# Copy_of_electretMicPreamp_-_THT.net
KiCad netlist of a schematic drawn in EAGLE
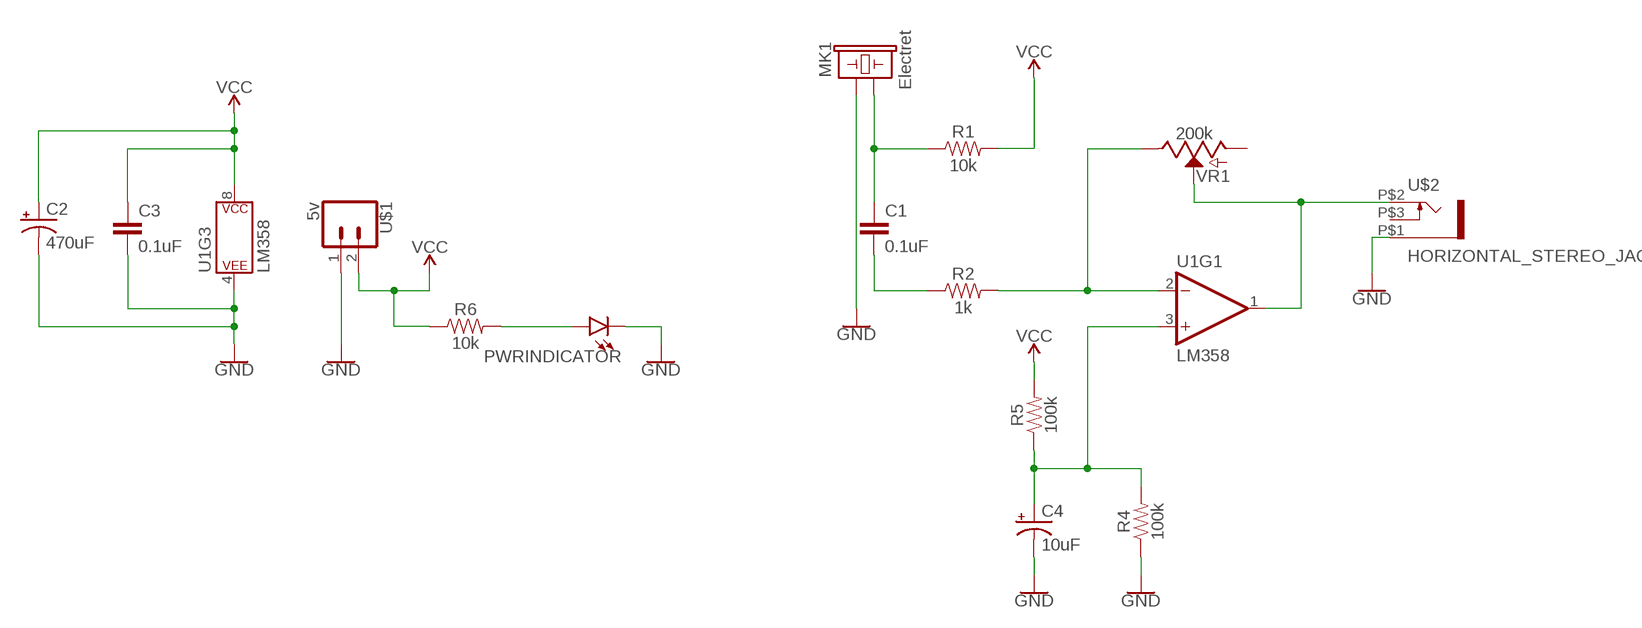
[diagram p0: schematic, sheet 1]

(export (version "E")
  (design (tool "Eeschema 10.0.6"))
  (components
    (comp (ref "C1")
      (value "0.1uF")
      (footprint "eagle-import:CAP-PTH-SMALL-KIT")
      (libsource (lib "eagle-import") (part "0.1UF-KIT-EZ-50V-20%"))
    )
    (comp (ref "C2")
      (value "470uF")
      (footprint "eagle-import:CPOL-RADIAL-2.5MM-5MM")
      (libsource (lib "eagle-import") (part "10UF-POLAR-RADIAL-2.5MM-25V-20%"))
    )
    (comp (ref "C3")
      (value "0.1uF")
      (footprint "eagle-import:CAP-PTH-SMALL-KIT")
      (libsource (lib "eagle-import") (part "0.1UF-KIT-EZ-50V-20%"))
    )
    (comp (ref "C4")
      (value "10uF")
      (footprint "eagle-import:CPOL-RADIAL-2.5MM-5MM")
      (libsource (lib "eagle-import") (part "10UF-POLAR-RADIAL-2.5MM-25V-20%"))
    )
    (comp (ref "MK1")
      (value "Electret")
      (footprint "eagle-import:MICROPHONE-PTH-9.7MM")
      (libsource (lib "eagle-import") (part "MIC-PTH"))
    )
    (comp (ref "PWRINDICATOR")
      (value "LED-3MM-NO_SILK")
      (footprint "eagle-import:LED_3MM-NS")
      (libsource (lib "eagle-import") (part "LED-3MM-NO_SILK"))
    )
    (comp (ref "R1")
      (value "10k")
      (footprint "eagle-import:AXIAL-0.3")
      (libsource (lib "eagle-import") (part "1KOHM-HORIZ-1/4W-5%"))
    )
    (comp (ref "R2")
      (value "1k")
      (footprint "eagle-import:AXIAL-0.3")
      (libsource (lib "eagle-import") (part "1KOHM-HORIZ-1/4W-5%"))
    )
    (comp (ref "R4")
      (value "100k")
      (footprint "eagle-import:AXIAL-0.3")
      (libsource (lib "eagle-import") (part "1KOHM-HORIZ-1/4W-5%"))
    )
    (comp (ref "R5")
      (value "100k")
      (footprint "eagle-import:AXIAL-0.3")
      (libsource (lib "eagle-import") (part "1KOHM-HORIZ-1/4W-5%"))
    )
    (comp (ref "R6")
      (value "10k")
      (footprint "eagle-import:AXIAL-0.3")
      (libsource (lib "eagle-import") (part "1KOHM-HORIZ-1/4W-5%"))
    )
    (comp (ref "U$1")
      (value "5v")
      (footprint "eagle-import:SCREWTERMINAL-2X1")
      (libsource (lib "eagle-import") (part "SCREWTERMINAL-1X2"))
    )
    (comp (ref "U$2")
      (value "HORIZONTAL_STEREO_JACK")
      (footprint "eagle-import:HORIZONTAL_STEREO_JACK")
      (libsource (lib "eagle-import") (part "HORIZONTAL_STERO_JACK"))
    )
    (comp (ref "U1")
      (value "LM358")
      (footprint "eagle-import:DIP08-KIT")
      (libsource (lib "eagle-import") (part "LM358KIT"))
    )
    (comp (ref "VR1")
      (value "200k")
      (footprint "eagle-import:POT-PTH-ALPS")
      (libsource (lib "eagle-import") (part "POTENTIOMETER-PTH-9MM-1/20W-20%"))
    )
  )
  (nets
    (net (code "1") (name "GND") (class "Default")
      (node (ref "C2") (pin "2") (pinfunction "-_2") (pintype "passive"))
      (node (ref "C3") (pin "2") (pinfunction "2_2") (pintype "passive"))
      (node (ref "C4") (pin "2") (pinfunction "-_2") (pintype "passive"))
      (node (ref "MK1") (pin "1") (pinfunction "1_1") (pintype "passive"))
      (node (ref "PWRINDICATOR") (pin "K") (pinfunction "C_K") (pintype "passive"))
      (node (ref "R4") (pin "P$1") (pinfunction "1_P$1") (pintype "passive"))
      (node (ref "U$1") (pin "1") (pinfunction "1_1") (pintype "passive"))
      (node (ref "U$2") (pin "P$1") (pinfunction "1_P$1") (pintype "passive"))
      (node (ref "U1") (pin "4") (pinfunction "P$V-_4") (pintype "bidirectional"))
    )
    (net (code "2") (name "Net-(C4-+)") (class "Default")
      (node (ref "C4") (pin "1") (pinfunction "+_1") (pintype "passive"))
      (node (ref "R4") (pin "P$2") (pinfunction "2_P$2") (pintype "passive"))
      (node (ref "R5") (pin "P$1") (pinfunction "1_P$1") (pintype "passive"))
      (node (ref "U1") (pin "3") (pinfunction "+IN_3") (pintype "input"))
    )
    (net (code "3") (name "Net-(R1-1)") (class "Default")
      (node (ref "C1") (pin "1") (pinfunction "1_1") (pintype "passive"))
      (node (ref "MK1") (pin "2") (pinfunction "2_2") (pintype "passive"))
      (node (ref "R1") (pin "P$1") (pinfunction "1_P$1") (pintype "passive"))
    )
    (net (code "4") (name "Net-(R2-1)") (class "Default")
      (node (ref "C1") (pin "2") (pinfunction "2_2") (pintype "passive"))
      (node (ref "R2") (pin "P$1") (pinfunction "1_P$1") (pintype "passive"))
    )
    (net (code "5") (name "Net-(R2-2)") (class "Default")
      (node (ref "R2") (pin "P$2") (pinfunction "2_P$2") (pintype "passive"))
      (node (ref "U1") (pin "2") (pinfunction "-IN_2") (pintype "input"))
      (node (ref "VR1") (pin "P$1") (pinfunction "E_P$1") (pintype "passive"))
    )
    (net (code "6") (name "Net-(R6-2)") (class "Default")
      (node (ref "PWRINDICATOR") (pin "A") (pinfunction "A_A") (pintype "passive"))
      (node (ref "R6") (pin "P$2") (pinfunction "2_P$2") (pintype "passive"))
    )
    (net (code "7") (name "Net-(U$2-2)") (class "Default")
      (node (ref "U$2") (pin "P$2") (pinfunction "2_P$2") (pintype "passive"))
      (node (ref "U1") (pin "1") (pinfunction "OUT_1") (pintype "output"))
      (node (ref "VR1") (pin "P$2") (pinfunction "S_P$2") (pintype "passive"))
    )
    (net (code "8") (name "VCC") (class "Default")
      (node (ref "C2") (pin "1") (pinfunction "+_1") (pintype "passive"))
      (node (ref "C3") (pin "1") (pinfunction "1_1") (pintype "passive"))
      (node (ref "R1") (pin "P$2") (pinfunction "2_P$2") (pintype "passive"))
      (node (ref "R5") (pin "P$2") (pinfunction "2_P$2") (pintype "passive"))
      (node (ref "R6") (pin "P$1") (pinfunction "1_P$1") (pintype "passive"))
      (node (ref "U$1") (pin "2") (pinfunction "2_2") (pintype "passive"))
      (node (ref "U1") (pin "8") (pinfunction "P$V+_8") (pintype "bidirectional"))
    )
    (net (code "9") (name "unconnected-(U$2-3-PadP$3)") (class "Default")
      (node (ref "U$2") (pin "P$3") (pinfunction "3_P$3") (pintype "passive"))
    )
    (net (code "10") (name "unconnected-(VR1-A-PadP$3)") (class "Default")
      (node (ref "VR1") (pin "P$3") (pinfunction "A_P$3") (pintype "passive"))
    )
  )
)
